# Sheet12.net
KiCad netlist of a schematic drawn in Altium Designer
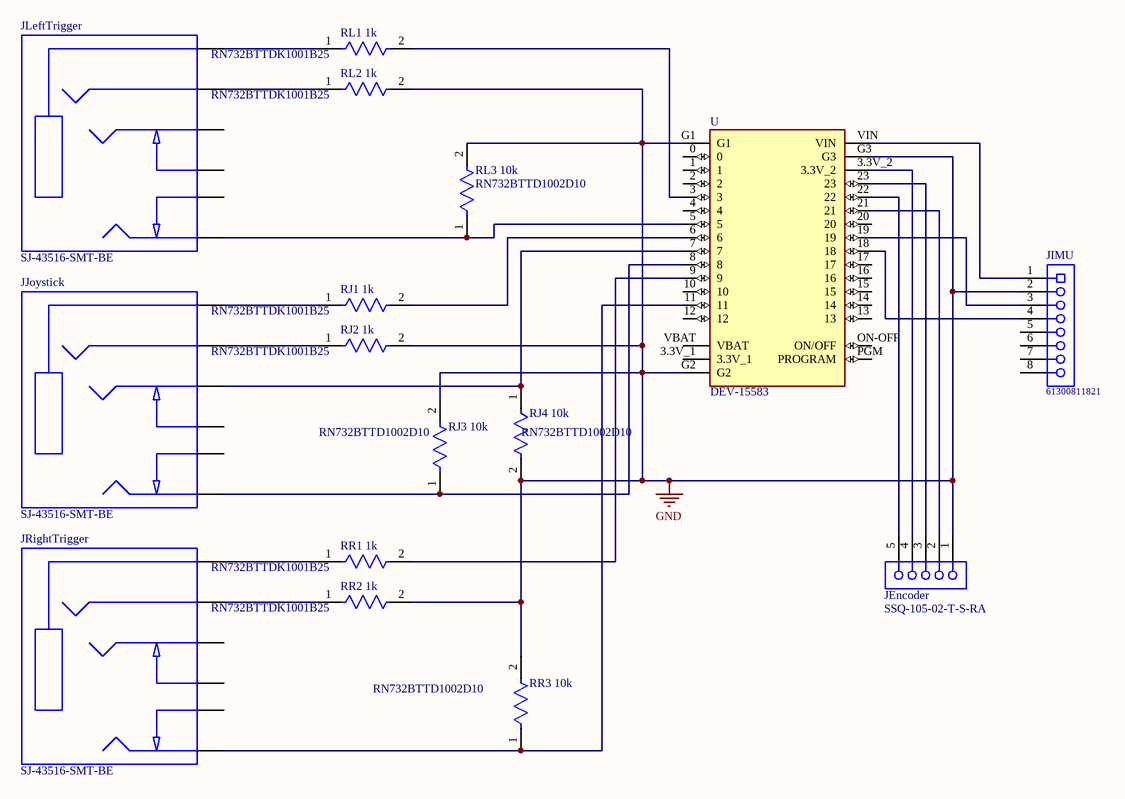
[diagram p0: Sheet12.SchDoc]

(export (version "E")
  (design (tool "Eeschema 10.0.6"))
  (components
    (comp (ref "JEncoder")
      (value "SSQ-105-02-T-S-RA")
      (footprint "SMTC-SSQ-105-02-X-S-RA")
      (description "SQ Post Socket, Through-hole, Right Angle, -55 to 105 degC, 2.54 mm Pitch, 5-Pin, Female, RoHS")
      (fields (field (name "MANUFACTURER") "Samtec"))
      (libsource (lib "Altium Content Vault") (part "SMTC-SSQ-105-02-X-S-RA"))
    )
    (comp (ref "JIMU")
      (value "61300811821")
      (footprint "61300811821")
      (description "THT Vertical Socket Header WR-PHD, Pitch 2.54 mm, Single Row, 8 pins")
      (fields (field (name "MANUFACTURER") "Wurth Elektronik") (field (name "PUBLISHER") "WurthElektronik"))
      (libsource (lib "Altium Content Vault") (part "WE-CN-1P-F-R8"))
    )
    (comp (ref "JJoystick")
      (value "SJ-43516-SMT-BE")
      (footprint "CUI_SJ-43516-SMT-BE")
      (description "3.5 mm, 4 Conductors, Right Angle, Surface Mount _SMT_, Audio Jack Connector")
      (fields (field (name "MP") "SJ-43516-SMT-TR-BE") (field (name "MF") "CUI Devices"))
      (libsource (lib "SJ-43516-SMT-BE") (part "SJ-43516-SMT-BE"))
    )
    (comp (ref "JLeftTrigger")
      (value "SJ-43516-SMT-BE")
      (footprint "CUI_SJ-43516-SMT-BE")
      (description "3.5 mm, 4 Conductors, Right Angle, Surface Mount _SMT_, Audio Jack Connector")
      (fields (field (name "MP") "SJ-43516-SMT-TR-BE") (field (name "MF") "CUI Devices"))
      (libsource (lib "SJ-43516-SMT-BE") (part "SJ-43516-SMT-BE"))
    )
    (comp (ref "JRightTrigger")
      (value "SJ-43516-SMT-BE")
      (footprint "CUI_SJ-43516-SMT-BE")
      (description "3.5 mm, 4 Conductors, Right Angle, Surface Mount _SMT_, Audio Jack Connector")
      (fields (field (name "MP") "SJ-43516-SMT-TR-BE") (field (name "MF") "CUI Devices"))
      (libsource (lib "SJ-43516-SMT-BE") (part "SJ-43516-SMT-BE"))
    )
    (comp (ref "RJ1 1k")
      (value "RN732BTTDK1001B25")
      (footprint "FP-RN732B-IPC_C")
      (description "1kΩ ±0.1% 0.125W, 1/8W Chip Resistor 1206 (3216 Metric) Moisture Resistant Thin Film")
      (fields (field (name "TOLERANCE") "0.1%"))
      (libsource (lib "Altium Content Vault") (part "1029c3af85768c4190bb7ad29bc67b5"))
    )
    (comp (ref "RJ2 1k")
      (value "RN732BTTDK1001B25")
      (footprint "FP-RN732B-IPC_C")
      (description "1kΩ ±0.1% 0.125W, 1/8W Chip Resistor 1206 (3216 Metric) Moisture Resistant Thin Film")
      (fields (field (name "TOLERANCE") "0.1%"))
      (libsource (lib "Altium Content Vault") (part "1029c3af85768c4190bb7ad29bc67b5"))
    )
    (comp (ref "RJ3 10k")
      (value "RN732BTTD1002D10")
      (footprint "FP-RN732B-IPC_B")
      (description "10kΩ ±0.5% 0.125W, 1/8W Chip Resistor 1206 (3216 Metric) Moisture Resistant Thin Film")
      (fields (field (name "TOLERANCE") "0.5%"))
      (libsource (lib "Altium Content Vault") (part "1029c3af85768c4190bb7ad29bc67b5"))
    )
    (comp (ref "RJ4 10k")
      (value "RN732BTTD1002D10")
      (footprint "FP-RN732B-IPC_B")
      (description "10kΩ ±0.5% 0.125W, 1/8W Chip Resistor 1206 (3216 Metric) Moisture Resistant Thin Film")
      (fields (field (name "TOLERANCE") "0.5%"))
      (libsource (lib "Altium Content Vault") (part "1029c3af85768c4190bb7ad29bc67b5"))
    )
    (comp (ref "RL1 1k")
      (value "RN732BTTDK1001B25")
      (footprint "FP-RN732B-IPC_C")
      (description "1kΩ ±0.1% 0.125W, 1/8W Chip Resistor 1206 (3216 Metric) Moisture Resistant Thin Film")
      (fields (field (name "TOLERANCE") "0.1%"))
      (libsource (lib "Altium Content Vault") (part "1029c3af85768c4190bb7ad29bc67b5"))
    )
    (comp (ref "RL2 1k")
      (value "RN732BTTDK1001B25")
      (footprint "FP-RN732B-IPC_C")
      (description "1kΩ ±0.1% 0.125W, 1/8W Chip Resistor 1206 (3216 Metric) Moisture Resistant Thin Film")
      (fields (field (name "TOLERANCE") "0.1%"))
      (libsource (lib "Altium Content Vault") (part "1029c3af85768c4190bb7ad29bc67b5"))
    )
    (comp (ref "RL3 10k")
      (value "RN732BTTD1002D10")
      (footprint "FP-RN732B-IPC_B")
      (description "10kΩ ±0.5% 0.125W, 1/8W Chip Resistor 1206 (3216 Metric) Moisture Resistant Thin Film")
      (fields (field (name "TOLERANCE") "0.5%"))
      (libsource (lib "Altium Content Vault") (part "1029c3af85768c4190bb7ad29bc67b5"))
    )
    (comp (ref "RR1 1k")
      (value "RN732BTTDK1001B25")
      (footprint "FP-RN732B-IPC_C")
      (description "1kΩ ±0.1% 0.125W, 1/8W Chip Resistor 1206 (3216 Metric) Moisture Resistant Thin Film")
      (fields (field (name "TOLERANCE") "0.1%"))
      (libsource (lib "Altium Content Vault") (part "1029c3af85768c4190bb7ad29bc67b5"))
    )
    (comp (ref "RR2 1k")
      (value "RN732BTTDK1001B25")
      (footprint "FP-RN732B-IPC_C")
      (description "1kΩ ±0.1% 0.125W, 1/8W Chip Resistor 1206 (3216 Metric) Moisture Resistant Thin Film")
      (fields (field (name "TOLERANCE") "0.1%"))
      (libsource (lib "Altium Content Vault") (part "1029c3af85768c4190bb7ad29bc67b5"))
    )
    (comp (ref "RR3 10k")
      (value "RN732BTTD1002D10")
      (footprint "FP-RN732B-IPC_B")
      (description "10kΩ ±0.5% 0.125W, 1/8W Chip Resistor 1206 (3216 Metric) Moisture Resistant Thin Film")
      (fields (field (name "TOLERANCE") "0.5%"))
      (libsource (lib "Altium Content Vault") (part "1029c3af85768c4190bb7ad29bc67b5"))
    )
    (comp (ref "U")
      (value "DEV-15583")
      (footprint "MODULE_DEV-15583")
      (description "RT1062 Teensy 4.0 i.MX ARMÂ® CortexÂ®-M7 MPU Embedded Evaluation Board")
      (fields
        (field (name "MF") "SparkFun Electronics")
        (field (name "DIGI-KEY_PART_NUMBER") "1568-DEV-15583-ND")
      )
      (libsource (lib "DEV-15583") (part "DEV-15583"))
    )
  )
  (nets
    (net (code "1") (name "GND") (class "Default")
      (node (ref "JEncoder") (pin "1") (pinfunction "1_1") (pintype "passive"))
      (node (ref "JIMU") (pin "2") (pinfunction "2_2") (pintype "passive"))
      (node (ref "RJ2 1k") (pin "2") (pinfunction "2_2") (pintype "passive"))
      (node (ref "RJ3 10k") (pin "2") (pinfunction "2_2") (pintype "passive"))
      (node (ref "RJ4 10k") (pin "2") (pinfunction "2_2") (pintype "passive"))
      (node (ref "RL2 1k") (pin "2") (pinfunction "2_2") (pintype "passive"))
      (node (ref "RL3 10k") (pin "2") (pinfunction "2_2") (pintype "passive"))
      (node (ref "RR2 1k") (pin "2") (pinfunction "2_2") (pintype "passive"))
      (node (ref "RR3 10k") (pin "2") (pinfunction "2_2") (pintype "passive"))
      (node (ref "U") (pin "G1") (pinfunction "G1_G1") (pintype "power_in"))
      (node (ref "U") (pin "G2") (pinfunction "G2_G2") (pintype "power_in"))
      (node (ref "U") (pin "G3") (pinfunction "G3_G3") (pintype "power_in"))
    )
    (net (code "2") (name "Net-(JEncoder-Pad2)") (class "Default")
      (node (ref "JEncoder") (pin "2") (pinfunction "2_2") (pintype "passive"))
      (node (ref "U") (pin "21") (pinfunction "21_21") (pintype "bidirectional"))
    )
    (net (code "3") (name "Net-(JEncoder-Pad3)") (class "Default")
      (node (ref "JEncoder") (pin "3") (pinfunction "3_3") (pintype "passive"))
      (node (ref "U") (pin "23") (pinfunction "23_23") (pintype "bidirectional"))
    )
    (net (code "4") (name "Net-(JEncoder-Pad4)") (class "Default")
      (node (ref "JEncoder") (pin "4") (pinfunction "4_4") (pintype "passive"))
      (node (ref "U") (pin "3.3V_2") (pinfunction "3.3V_2_3.3V_2") (pintype "power_in"))
    )
    (net (code "5") (name "Net-(JEncoder-Pad5)") (class "Default")
      (node (ref "JEncoder") (pin "5") (pinfunction "5_5") (pintype "passive"))
      (node (ref "U") (pin "22") (pinfunction "22_22") (pintype "bidirectional"))
    )
    (net (code "6") (name "Net-(JIMU-Pad1)") (class "Default")
      (node (ref "JIMU") (pin "1") (pinfunction "1_1") (pintype "passive"))
      (node (ref "U") (pin "VIN") (pinfunction "VIN_VIN") (pintype "power_in"))
    )
    (net (code "7") (name "Net-(JIMU-Pad3)") (class "Default")
      (node (ref "JIMU") (pin "3") (pinfunction "3_3") (pintype "passive"))
      (node (ref "U") (pin "19") (pinfunction "19_19") (pintype "bidirectional"))
    )
    (net (code "8") (name "Net-(JIMU-Pad4)") (class "Default")
      (node (ref "JIMU") (pin "4") (pinfunction "4_4") (pintype "passive"))
      (node (ref "U") (pin "18") (pinfunction "18_18") (pintype "bidirectional"))
    )
    (net (code "9") (name "Net-(JJoystick-RING1)") (class "Default")
      (node (ref "JJoystick") (pin "3") (pinfunction "RING1_3") (pintype "passive"))
      (node (ref "RJ4 10k") (pin "1") (pinfunction "1_1") (pintype "passive"))
      (node (ref "U") (pin "7") (pinfunction "7_7") (pintype "bidirectional"))
    )
    (net (code "10") (name "Net-(JJoystick-RING2)") (class "Default")
      (node (ref "JJoystick") (pin "4") (pinfunction "RING2_4") (pintype "passive"))
      (node (ref "RJ2 1k") (pin "1") (pinfunction "1_1") (pintype "passive"))
    )
    (net (code "11") (name "Net-(JJoystick-SLEEVE)") (class "Default")
      (node (ref "JJoystick") (pin "1") (pinfunction "SLEEVE_1") (pintype "passive"))
      (node (ref "RJ1 1k") (pin "1") (pinfunction "1_1") (pintype "passive"))
    )
    (net (code "12") (name "Net-(JJoystick-TIP)") (class "Default")
      (node (ref "JJoystick") (pin "2") (pinfunction "TIP_2") (pintype "passive"))
      (node (ref "RJ3 10k") (pin "1") (pinfunction "1_1") (pintype "passive"))
      (node (ref "U") (pin "8") (pinfunction "8_8") (pintype "bidirectional"))
    )
    (net (code "13") (name "Net-(JLeftTrigger-RING2)") (class "Default")
      (node (ref "JLeftTrigger") (pin "4") (pinfunction "RING2_4") (pintype "passive"))
      (node (ref "RL2 1k") (pin "1") (pinfunction "1_1") (pintype "passive"))
    )
    (net (code "14") (name "Net-(JLeftTrigger-SLEEVE)") (class "Default")
      (node (ref "JLeftTrigger") (pin "1") (pinfunction "SLEEVE_1") (pintype "passive"))
      (node (ref "RL1 1k") (pin "1") (pinfunction "1_1") (pintype "passive"))
    )
    (net (code "15") (name "Net-(JLeftTrigger-TIP)") (class "Default")
      (node (ref "JLeftTrigger") (pin "2") (pinfunction "TIP_2") (pintype "passive"))
      (node (ref "RL3 10k") (pin "1") (pinfunction "1_1") (pintype "passive"))
      (node (ref "U") (pin "5") (pinfunction "5_5") (pintype "bidirectional"))
    )
    (net (code "16") (name "Net-(JRightTrigger-RING2)") (class "Default")
      (node (ref "JRightTrigger") (pin "4") (pinfunction "RING2_4") (pintype "passive"))
      (node (ref "RR2 1k") (pin "1") (pinfunction "1_1") (pintype "passive"))
    )
    (net (code "17") (name "Net-(JRightTrigger-SLEEVE)") (class "Default")
      (node (ref "JRightTrigger") (pin "1") (pinfunction "SLEEVE_1") (pintype "passive"))
      (node (ref "RR1 1k") (pin "1") (pinfunction "1_1") (pintype "passive"))
    )
    (net (code "18") (name "Net-(JRightTrigger-TIP)") (class "Default")
      (node (ref "JRightTrigger") (pin "2") (pinfunction "TIP_2") (pintype "passive"))
      (node (ref "RR3 10k") (pin "1") (pinfunction "1_1") (pintype "passive"))
      (node (ref "U") (pin "11") (pinfunction "11_11") (pintype "bidirectional"))
    )
    (net (code "19") (name "Net-(RJ1 1k-Pad2)") (class "Default")
      (node (ref "RJ1 1k") (pin "2") (pinfunction "2_2") (pintype "passive"))
      (node (ref "U") (pin "6") (pinfunction "6_6") (pintype "bidirectional"))
    )
    (net (code "20") (name "Net-(RL1 1k-Pad2)") (class "Default")
      (node (ref "RL1 1k") (pin "2") (pinfunction "2_2") (pintype "passive"))
      (node (ref "U") (pin "3") (pinfunction "3_3") (pintype "bidirectional"))
    )
    (net (code "21") (name "Net-(RR1 1k-Pad2)") (class "Default")
      (node (ref "RR1 1k") (pin "2") (pinfunction "2_2") (pintype "passive"))
      (node (ref "U") (pin "9") (pinfunction "9_9") (pintype "bidirectional"))
    )
    (net (code "22") (name "unconnected-(JIMU-Pad5)") (class "Default")
      (node (ref "JIMU") (pin "5") (pinfunction "5_5") (pintype "passive"))
    )
    (net (code "23") (name "unconnected-(JIMU-Pad6)") (class "Default")
      (node (ref "JIMU") (pin "6") (pinfunction "6_6") (pintype "passive"))
    )
    (net (code "24") (name "unconnected-(JIMU-Pad7)") (class "Default")
      (node (ref "JIMU") (pin "7") (pinfunction "7_7") (pintype "passive"))
    )
    (net (code "25") (name "unconnected-(JIMU-Pad8)") (class "Default")
      (node (ref "JIMU") (pin "8") (pinfunction "8_8") (pintype "passive"))
    )
    (net (code "26") (name "unconnected-(JJoystick-RING_SWITCH-Pad6)") (class "Default")
      (node (ref "JJoystick") (pin "6") (pinfunction "RING_SWITCH_6") (pintype "passive"))
    )
    (net (code "27") (name "unconnected-(JJoystick-TIP_SWITCH-Pad5)") (class "Default")
      (node (ref "JJoystick") (pin "5") (pinfunction "TIP_SWITCH_5") (pintype "passive"))
    )
    (net (code "28") (name "unconnected-(JLeftTrigger-RING1-Pad3)") (class "Default")
      (node (ref "JLeftTrigger") (pin "3") (pinfunction "RING1_3") (pintype "passive"))
    )
    (net (code "29") (name "unconnected-(JLeftTrigger-RING_SWITCH-Pad6)") (class "Default")
      (node (ref "JLeftTrigger") (pin "6") (pinfunction "RING_SWITCH_6") (pintype "passive"))
    )
    (net (code "30") (name "unconnected-(JLeftTrigger-TIP_SWITCH-Pad5)") (class "Default")
      (node (ref "JLeftTrigger") (pin "5") (pinfunction "TIP_SWITCH_5") (pintype "passive"))
    )
    (net (code "31") (name "unconnected-(JRightTrigger-RING1-Pad3)") (class "Default")
      (node (ref "JRightTrigger") (pin "3") (pinfunction "RING1_3") (pintype "passive"))
    )
    (net (code "32") (name "unconnected-(JRightTrigger-RING_SWITCH-Pad6)") (class "Default")
      (node (ref "JRightTrigger") (pin "6") (pinfunction "RING_SWITCH_6") (pintype "passive"))
    )
    (net (code "33") (name "unconnected-(JRightTrigger-TIP_SWITCH-Pad5)") (class "Default")
      (node (ref "JRightTrigger") (pin "5") (pinfunction "TIP_SWITCH_5") (pintype "passive"))
    )
    (net (code "34") (name "unconnected-(U-ON{slash}OFF-PadON-OFF)") (class "Default")
      (node (ref "U") (pin "ON-OFF") (pinfunction "ON/OFF_ON-OFF") (pintype "bidirectional"))
    )
    (net (code "35") (name "unconnected-(U-PROGRAM-PadPGM)") (class "Default")
      (node (ref "U") (pin "PGM") (pinfunction "PROGRAM_PGM") (pintype "bidirectional"))
    )
    (net (code "36") (name "unconnected-(U-Pad0)") (class "Default")
      (node (ref "U") (pin "0") (pinfunction "0_0") (pintype "bidirectional"))
    )
    (net (code "37") (name "unconnected-(U-Pad1)") (class "Default")
      (node (ref "U") (pin "1") (pinfunction "1_1") (pintype "bidirectional"))
    )
    (net (code "38") (name "unconnected-(U-Pad2)") (class "Default")
      (node (ref "U") (pin "2") (pinfunction "2_2") (pintype "bidirectional"))
    )
    (net (code "39") (name "unconnected-(U-Pad3.3V_1)") (class "Default")
      (node (ref "U") (pin "3.3V_1") (pinfunction "3.3V_1_3.3V_1") (pintype "power_in"))
    )
    (net (code "40") (name "unconnected-(U-Pad4)") (class "Default")
      (node (ref "U") (pin "4") (pinfunction "4_4") (pintype "bidirectional"))
    )
    (net (code "41") (name "unconnected-(U-Pad10)") (class "Default")
      (node (ref "U") (pin "10") (pinfunction "10_10") (pintype "bidirectional"))
    )
    (net (code "42") (name "unconnected-(U-Pad12)") (class "Default")
      (node (ref "U") (pin "12") (pinfunction "12_12") (pintype "bidirectional"))
    )
    (net (code "43") (name "unconnected-(U-Pad13)") (class "Default")
      (node (ref "U") (pin "13") (pinfunction "13_13") (pintype "bidirectional"))
    )
    (net (code "44") (name "unconnected-(U-Pad14)") (class "Default")
      (node (ref "U") (pin "14") (pinfunction "14_14") (pintype "bidirectional"))
    )
    (net (code "45") (name "unconnected-(U-Pad15)") (class "Default")
      (node (ref "U") (pin "15") (pinfunction "15_15") (pintype "bidirectional"))
    )
    (net (code "46") (name "unconnected-(U-Pad16)") (class "Default")
      (node (ref "U") (pin "16") (pinfunction "16_16") (pintype "bidirectional"))
    )
    (net (code "47") (name "unconnected-(U-Pad17)") (class "Default")
      (node (ref "U") (pin "17") (pinfunction "17_17") (pintype "bidirectional"))
    )
    (net (code "48") (name "unconnected-(U-Pad20)") (class "Default")
      (node (ref "U") (pin "20") (pinfunction "20_20") (pintype "bidirectional"))
    )
    (net (code "49") (name "unconnected-(U-PadVBAT)") (class "Default")
      (node (ref "U") (pin "VBAT") (pinfunction "VBAT_VBAT") (pintype "power_in"))
    )
  )
)
